# Speaker_System_Board.net
KiCad netlist of a schematic drawn in EAGLE
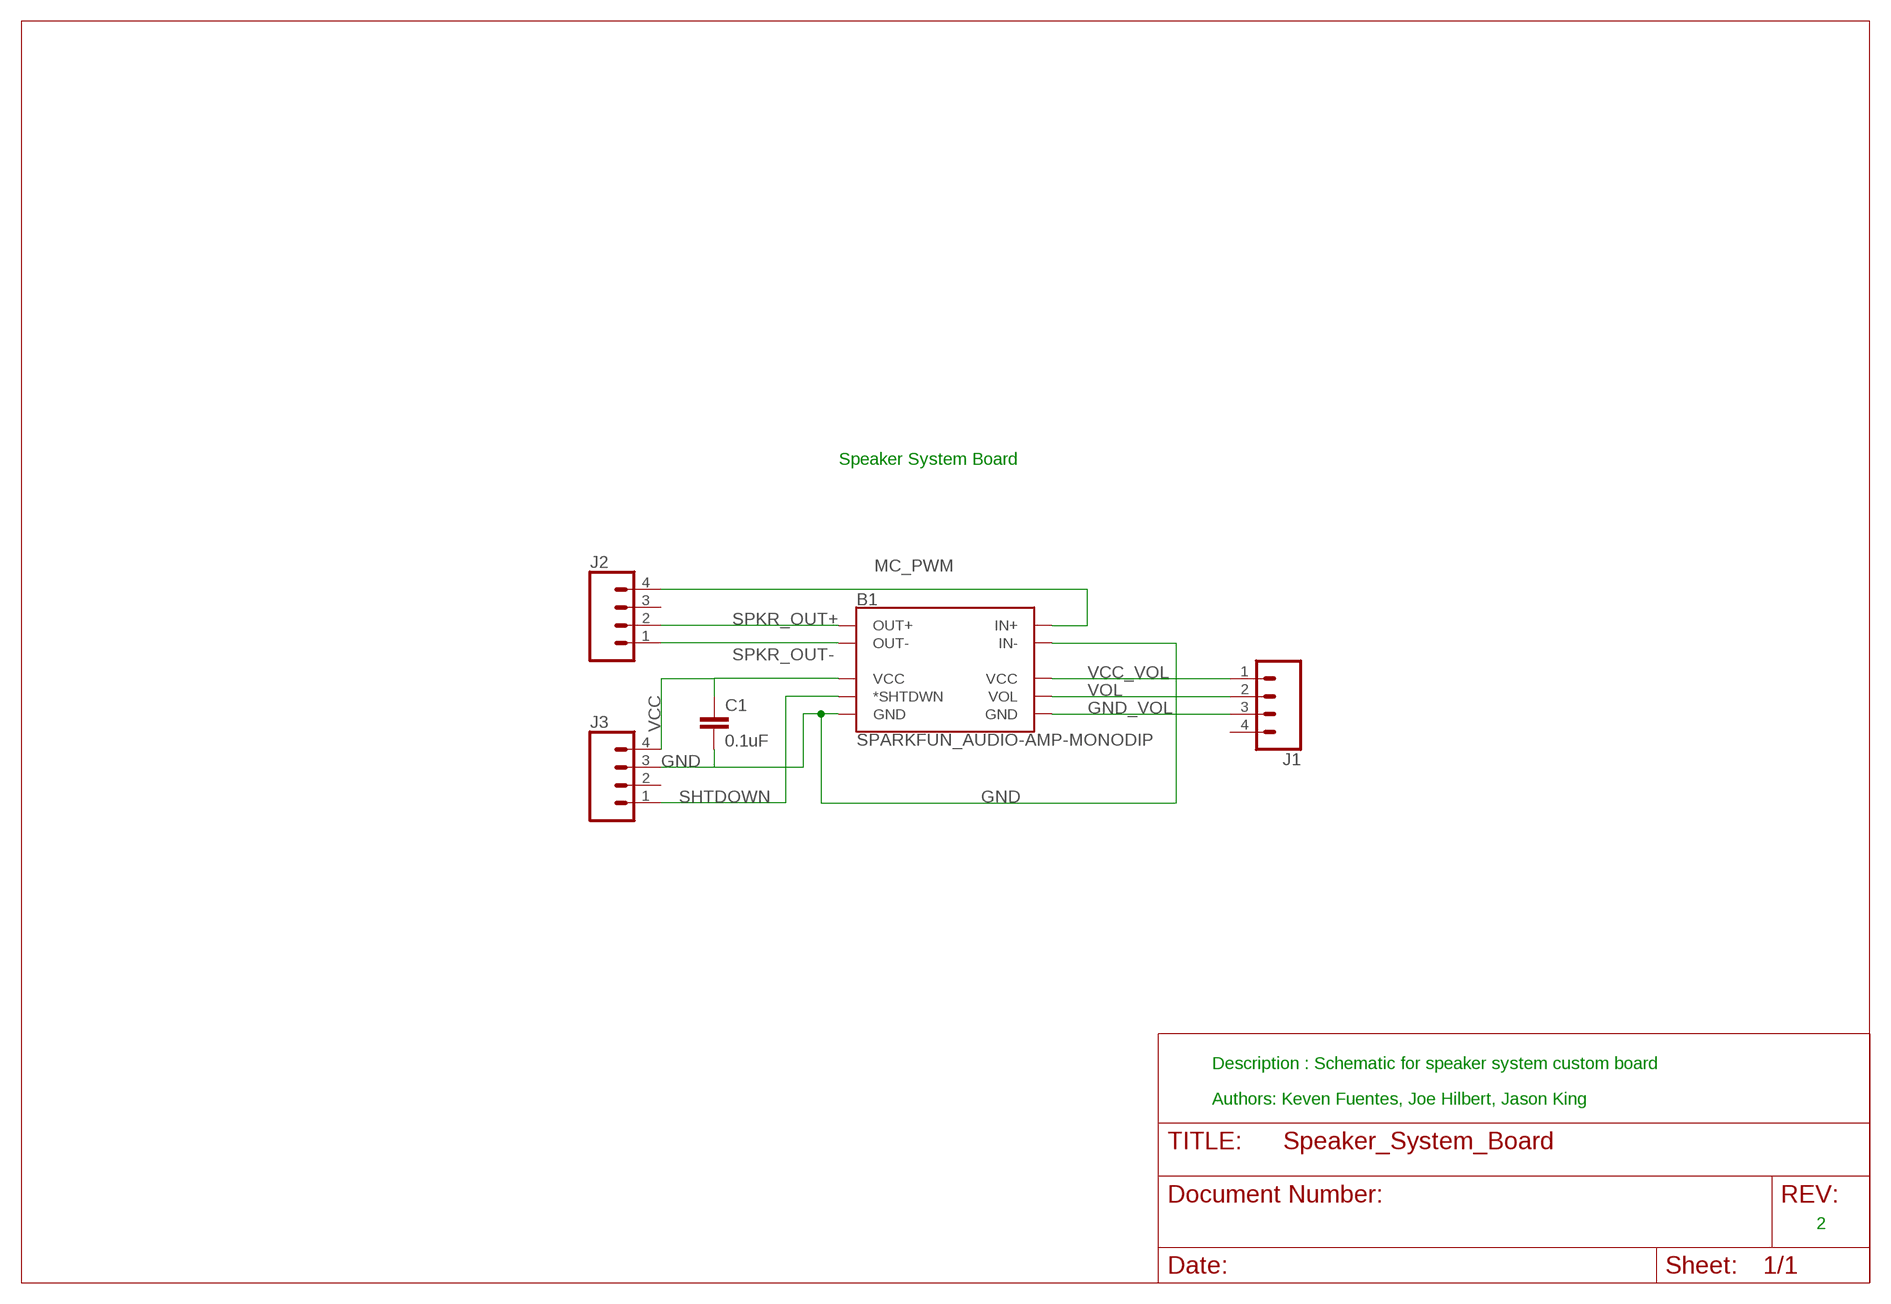
[diagram p0: schematic, sheet 1]

(export (version "E")
  (design (tool "Eeschema 10.0.6"))
  (components
    (comp (ref "B1")
      (value "SPARKFUN_AUDIO-AMP-MONODIP")
      (footprint "eagle-import:AUDIO-AMP-MONO")
      (libsource (lib "eagle-import") (part "SPARKFUN_AUDIO-AMP-MONODIP"))
    )
    (comp (ref "C1")
      (value "0.1uF")
      (footprint "eagle-import:0603")
      (libsource (lib "eagle-import") (part "0.1UF-0603-25V-(+80/-20%)"))
    )
    (comp (ref "J1")
      (value "CONN_04")
      (footprint "eagle-import:1X04")
      (libsource (lib "eagle-import") (part "CONN_04"))
    )
    (comp (ref "J2")
      (value "CONN_04")
      (footprint "eagle-import:1X04")
      (libsource (lib "eagle-import") (part "CONN_04"))
    )
    (comp (ref "J3")
      (value "CONN_04")
      (footprint "eagle-import:1X04")
      (libsource (lib "eagle-import") (part "CONN_04"))
    )
  )
  (nets
    (net (code "1") (name "/GND") (class "Default")
      (node (ref "B1") (pin "IN-") (pinfunction "IN-_IN-") (pintype "bidirectional"))
      (node (ref "B1") (pin "PWR-") (pinfunction "GND_PWR-") (pintype "bidirectional"))
      (node (ref "C1") (pin "2") (pinfunction "2_2") (pintype "passive"))
      (node (ref "J3") (pin "3") (pinfunction "3_3") (pintype "passive"))
    )
    (net (code "2") (name "/GND_VOL") (class "Default")
      (node (ref "B1") (pin "VOL-") (pinfunction "GND_VOL-") (pintype "bidirectional"))
      (node (ref "J1") (pin "3") (pinfunction "3_3") (pintype "passive"))
    )
    (net (code "3") (name "/MC_PWM") (class "Default")
      (node (ref "B1") (pin "IN+") (pinfunction "IN+_IN+") (pintype "bidirectional"))
      (node (ref "J2") (pin "4") (pinfunction "4_4") (pintype "passive"))
    )
    (net (code "4") (name "/SHTDOWN") (class "Default")
      (node (ref "B1") (pin "S") (pinfunction "*SHTDWN_S") (pintype "bidirectional"))
      (node (ref "J3") (pin "1") (pinfunction "1_1") (pintype "passive"))
    )
    (net (code "5") (name "/SPKR_OUT+") (class "Default")
      (node (ref "B1") (pin "OUT+") (pinfunction "OUT+_OUT+") (pintype "bidirectional"))
      (node (ref "J2") (pin "2") (pinfunction "2_2") (pintype "passive"))
    )
    (net (code "6") (name "/SPKR_OUT-") (class "Default")
      (node (ref "B1") (pin "OUT-") (pinfunction "OUT-_OUT-") (pintype "bidirectional"))
      (node (ref "J2") (pin "1") (pinfunction "1_1") (pintype "passive"))
    )
    (net (code "7") (name "/VCC") (class "Default")
      (node (ref "B1") (pin "PWR+") (pinfunction "VCC_PWR+") (pintype "bidirectional"))
      (node (ref "C1") (pin "1") (pinfunction "1_1") (pintype "passive"))
      (node (ref "J3") (pin "4") (pinfunction "4_4") (pintype "passive"))
    )
    (net (code "8") (name "/VCC_VOL") (class "Default")
      (node (ref "B1") (pin "VOL+") (pinfunction "VCC_VOL+") (pintype "bidirectional"))
      (node (ref "J1") (pin "1") (pinfunction "1_1") (pintype "passive"))
    )
    (net (code "9") (name "/VOL") (class "Default")
      (node (ref "B1") (pin "VOL") (pinfunction "VOL_VOL") (pintype "bidirectional"))
      (node (ref "J1") (pin "2") (pinfunction "2_2") (pintype "passive"))
    )
    (net (code "10") (name "unconnected-(J1-Pad4)") (class "Default")
      (node (ref "J1") (pin "4") (pinfunction "4_4") (pintype "passive"))
    )
    (net (code "11") (name "unconnected-(J2-Pad3)") (class "Default")
      (node (ref "J2") (pin "3") (pinfunction "3_3") (pintype "passive"))
    )
    (net (code "12") (name "unconnected-(J3-Pad2)") (class "Default")
      (node (ref "J3") (pin "2") (pinfunction "2_2") (pintype "passive"))
    )
  )
)
